# simple_thermostat_2.net
KiCad netlist of a schematic drawn in EAGLE
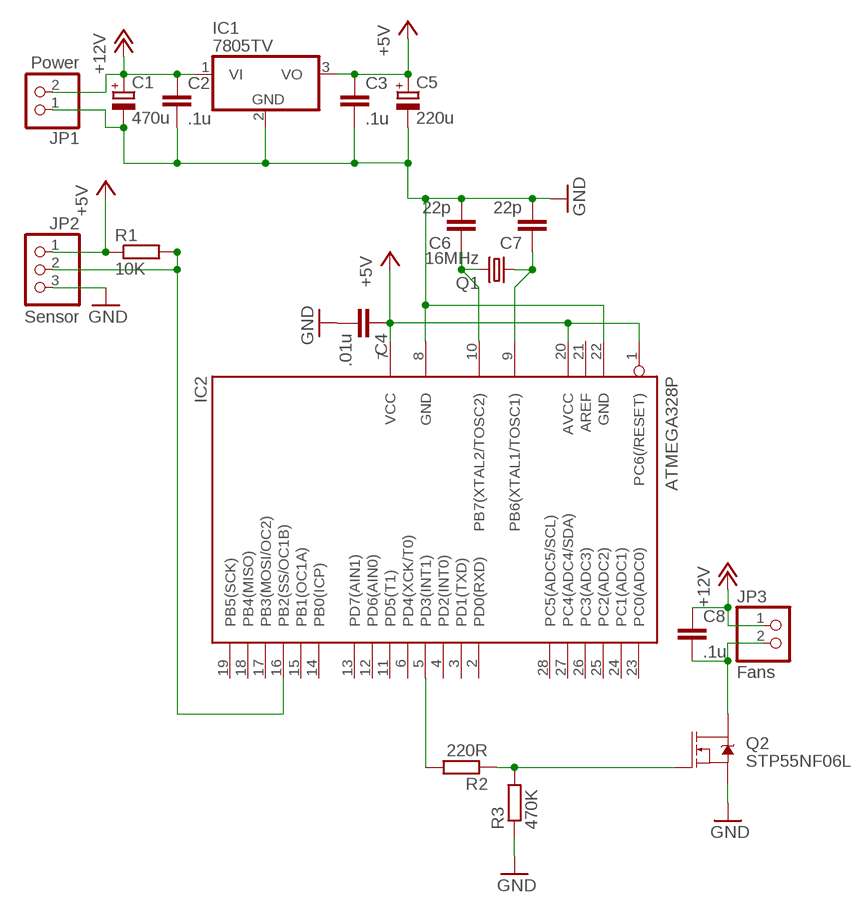
[diagram p0: schematic, sheet 1]

(export (version "E")
  (design (tool "Eeschema 10.0.6"))
  (components
    (comp (ref "C1")
      (value "470u")
      (footprint "eagle-import:E3,5-10")
      (libsource (lib "eagle-import") (part "CPOL-EUE3.5-10"))
    )
    (comp (ref "C2")
      (value ".1u")
      (footprint "eagle-import:C025-024X044")
      (libsource (lib "eagle-import") (part "C-EU025-024X044"))
    )
    (comp (ref "C3")
      (value ".1u")
      (footprint "eagle-import:C025-024X044")
      (libsource (lib "eagle-import") (part "C-EU025-024X044"))
    )
    (comp (ref "C4")
      (value ".01u")
      (footprint "eagle-import:C025-024X044")
      (libsource (lib "eagle-import") (part "C-EU025-024X044"))
    )
    (comp (ref "C5")
      (value "220u")
      (footprint "eagle-import:E2,5-7")
      (libsource (lib "eagle-import") (part "CPOL-EUE2.5-7"))
    )
    (comp (ref "C6")
      (value "22p")
      (footprint "eagle-import:C025-024X044")
      (libsource (lib "eagle-import") (part "C-EU025-024X044"))
    )
    (comp (ref "C7")
      (value "22p")
      (footprint "eagle-import:C025-024X044")
      (libsource (lib "eagle-import") (part "C-EU025-024X044"))
    )
    (comp (ref "C8")
      (value ".1u")
      (footprint "eagle-import:C025-024X044")
      (libsource (lib "eagle-import") (part "C-EU025-024X044"))
    )
    (comp (ref "IC1")
      (value "7805TV")
      (footprint "eagle-import:TO220V")
      (libsource (lib "eagle-import") (part "78TV05"))
    )
    (comp (ref "IC2")
      (value "ATMEGA328P")
      (footprint "eagle-import:DIL28-3")
      (libsource (lib "eagle-import") (part "MEGA8-P"))
    )
    (comp (ref "JP1")
      (value "Power")
      (footprint "eagle-import:1X02")
      (libsource (lib "eagle-import") (part "PINHD-1X2"))
    )
    (comp (ref "JP2")
      (value "Sensor")
      (footprint "eagle-import:1X03")
      (libsource (lib "eagle-import") (part "PINHD-1X3"))
    )
    (comp (ref "JP3")
      (value "Fans")
      (footprint "eagle-import:1X02")
      (libsource (lib "eagle-import") (part "PINHD-1X2"))
    )
    (comp (ref "Q1")
      (value "16MHz")
      (footprint "eagle-import:HC18U-V")
      (libsource (lib "eagle-import") (part "CRYSTALHC18U-V"))
    )
    (comp (ref "Q2")
      (value "STP55NF06L")
      (footprint "eagle-import:TO220V")
      (libsource (lib "eagle-import") (part "MOSFET-NCH-FQP30N06L"))
    )
    (comp (ref "R1")
      (value "10K")
      (footprint "eagle-import:0207_7")
      (libsource (lib "eagle-import") (part "R-EU_0207/7"))
    )
    (comp (ref "R2")
      (value "220R")
      (footprint "eagle-import:0207_7")
      (libsource (lib "eagle-import") (part "R-EU_0207/7"))
    )
    (comp (ref "R3")
      (value "470K")
      (footprint "eagle-import:0207_7")
      (libsource (lib "eagle-import") (part "R-EU_0207/7"))
    )
  )
  (nets
    (net (code "1") (name "+5V") (class "Default")
      (node (ref "C3") (pin "1") (pinfunction "1_1") (pintype "passive"))
      (node (ref "C4") (pin "1") (pinfunction "1_1") (pintype "passive"))
      (node (ref "C5") (pin "+") (pinfunction "+_+") (pintype "passive"))
      (node (ref "IC1") (pin "3") (pinfunction "VO_3") (pintype "passive"))
      (node (ref "IC2") (pin "1") (pinfunction "PC6(/RESET)_1") (pintype "bidirectional"))
      (node (ref "IC2") (pin "20") (pinfunction "AVCC_20") (pintype "power_in"))
      (node (ref "IC2") (pin "7") (pinfunction "VCC_7") (pintype "power_in"))
      (node (ref "JP2") (pin "1") (pinfunction "1_1") (pintype "passive"))
      (node (ref "R1") (pin "1") (pinfunction "1_1") (pintype "passive"))
    )
    (net (code "2") (name "+12V") (class "Default")
      (node (ref "C1") (pin "+") (pinfunction "+_+") (pintype "passive"))
      (node (ref "C2") (pin "1") (pinfunction "1_1") (pintype "passive"))
      (node (ref "C8") (pin "1") (pinfunction "1_1") (pintype "passive"))
      (node (ref "IC1") (pin "1") (pinfunction "VI_1") (pintype "input"))
      (node (ref "JP1") (pin "2") (pinfunction "2_2") (pintype "passive"))
      (node (ref "JP3") (pin "1") (pinfunction "1_1") (pintype "passive"))
    )
    (net (code "3") (name "GND") (class "Default")
      (node (ref "C1") (pin "-") (pinfunction "-_-") (pintype "passive"))
      (node (ref "C2") (pin "2") (pinfunction "2_2") (pintype "passive"))
      (node (ref "C3") (pin "2") (pinfunction "2_2") (pintype "passive"))
      (node (ref "C4") (pin "2") (pinfunction "2_2") (pintype "passive"))
      (node (ref "C5") (pin "-") (pinfunction "-_-") (pintype "passive"))
      (node (ref "C6") (pin "2") (pinfunction "2_2") (pintype "passive"))
      (node (ref "C7") (pin "2") (pinfunction "2_2") (pintype "passive"))
      (node (ref "IC1") (pin "2") (pinfunction "GND_2") (pintype "passive"))
      (node (ref "IC2") (pin "22") (pinfunction "GND_22") (pintype "power_in"))
      (node (ref "IC2") (pin "8") (pinfunction "GND_8") (pintype "power_in"))
      (node (ref "JP1") (pin "1") (pinfunction "1_1") (pintype "passive"))
      (node (ref "JP2") (pin "3") (pinfunction "3_3") (pintype "passive"))
      (node (ref "Q2") (pin "3") (pinfunction "S_3") (pintype "bidirectional"))
      (node (ref "R3") (pin "1") (pinfunction "1_1") (pintype "passive"))
    )
    (net (code "4") (name "Net-(IC2-PB2(SS{slash}OC1B))") (class "Default")
      (node (ref "IC2") (pin "16") (pinfunction "PB2(SS/OC1B)_16") (pintype "bidirectional"))
      (node (ref "JP2") (pin "2") (pinfunction "2_2") (pintype "passive"))
      (node (ref "R1") (pin "2") (pinfunction "2_2") (pintype "passive"))
    )
    (net (code "5") (name "Net-(IC2-PB6(XTAL1{slash}TOSC1))") (class "Default")
      (node (ref "C7") (pin "1") (pinfunction "1_1") (pintype "passive"))
      (node (ref "IC2") (pin "9") (pinfunction "PB6(XTAL1/TOSC1)_9") (pintype "bidirectional"))
      (node (ref "Q1") (pin "1") (pinfunction "1_1") (pintype "passive"))
    )
    (net (code "6") (name "Net-(IC2-PB7(XTAL2{slash}TOSC2))") (class "Default")
      (node (ref "C6") (pin "1") (pinfunction "1_1") (pintype "passive"))
      (node (ref "IC2") (pin "10") (pinfunction "PB7(XTAL2/TOSC2)_10") (pintype "bidirectional"))
      (node (ref "Q1") (pin "2") (pinfunction "2_2") (pintype "passive"))
    )
    (net (code "7") (name "Net-(IC2-PD3(INT1))") (class "Default")
      (node (ref "IC2") (pin "5") (pinfunction "PD3(INT1)_5") (pintype "bidirectional"))
      (node (ref "R2") (pin "2") (pinfunction "2_2") (pintype "passive"))
    )
    (net (code "8") (name "Net-(Q2-D)") (class "Default")
      (node (ref "C8") (pin "2") (pinfunction "2_2") (pintype "passive"))
      (node (ref "JP3") (pin "2") (pinfunction "2_2") (pintype "passive"))
      (node (ref "Q2") (pin "2") (pinfunction "D_2") (pintype "bidirectional"))
    )
    (net (code "9") (name "Net-(Q2-G)") (class "Default")
      (node (ref "Q2") (pin "1") (pinfunction "G_1") (pintype "bidirectional"))
      (node (ref "R2") (pin "1") (pinfunction "1_1") (pintype "passive"))
      (node (ref "R3") (pin "2") (pinfunction "2_2") (pintype "passive"))
    )
    (net (code "10") (name "unconnected-(IC2-AREF-Pad21)") (class "Default")
      (node (ref "IC2") (pin "21") (pinfunction "AREF_21") (pintype "passive"))
    )
    (net (code "11") (name "unconnected-(IC2-PB0(ICP)-Pad14)") (class "Default")
      (node (ref "IC2") (pin "14") (pinfunction "PB0(ICP)_14") (pintype "bidirectional"))
    )
    (net (code "12") (name "unconnected-(IC2-PB1(OC1A)-Pad15)") (class "Default")
      (node (ref "IC2") (pin "15") (pinfunction "PB1(OC1A)_15") (pintype "bidirectional"))
    )
    (net (code "13") (name "unconnected-(IC2-PB3(MOSI{slash}OC2)-Pad17)") (class "Default")
      (node (ref "IC2") (pin "17") (pinfunction "PB3(MOSI/OC2)_17") (pintype "bidirectional"))
    )
    (net (code "14") (name "unconnected-(IC2-PB4(MISO)-Pad18)") (class "Default")
      (node (ref "IC2") (pin "18") (pinfunction "PB4(MISO)_18") (pintype "bidirectional"))
    )
    (net (code "15") (name "unconnected-(IC2-PB5(SCK)-Pad19)") (class "Default")
      (node (ref "IC2") (pin "19") (pinfunction "PB5(SCK)_19") (pintype "bidirectional"))
    )
    (net (code "16") (name "unconnected-(IC2-PC0(ADC0)-Pad23)") (class "Default")
      (node (ref "IC2") (pin "23") (pinfunction "PC0(ADC0)_23") (pintype "bidirectional"))
    )
    (net (code "17") (name "unconnected-(IC2-PC1(ADC1)-Pad24)") (class "Default")
      (node (ref "IC2") (pin "24") (pinfunction "PC1(ADC1)_24") (pintype "bidirectional"))
    )
    (net (code "18") (name "unconnected-(IC2-PC2(ADC2)-Pad25)") (class "Default")
      (node (ref "IC2") (pin "25") (pinfunction "PC2(ADC2)_25") (pintype "bidirectional"))
    )
    (net (code "19") (name "unconnected-(IC2-PC3(ADC3)-Pad26)") (class "Default")
      (node (ref "IC2") (pin "26") (pinfunction "PC3(ADC3)_26") (pintype "bidirectional"))
    )
    (net (code "20") (name "unconnected-(IC2-PC4(ADC4{slash}SDA)-Pad27)") (class "Default")
      (node (ref "IC2") (pin "27") (pinfunction "PC4(ADC4/SDA)_27") (pintype "bidirectional"))
    )
    (net (code "21") (name "unconnected-(IC2-PC5(ADC5{slash}SCL)-Pad28)") (class "Default")
      (node (ref "IC2") (pin "28") (pinfunction "PC5(ADC5/SCL)_28") (pintype "bidirectional"))
    )
    (net (code "22") (name "unconnected-(IC2-PD0(RXD)-Pad2)") (class "Default")
      (node (ref "IC2") (pin "2") (pinfunction "PD0(RXD)_2") (pintype "bidirectional"))
    )
    (net (code "23") (name "unconnected-(IC2-PD1(TXD)-Pad3)") (class "Default")
      (node (ref "IC2") (pin "3") (pinfunction "PD1(TXD)_3") (pintype "bidirectional"))
    )
    (net (code "24") (name "unconnected-(IC2-PD2(INT0)-Pad4)") (class "Default")
      (node (ref "IC2") (pin "4") (pinfunction "PD2(INT0)_4") (pintype "bidirectional"))
    )
    (net (code "25") (name "unconnected-(IC2-PD4(XCK{slash}T0)-Pad6)") (class "Default")
      (node (ref "IC2") (pin "6") (pinfunction "PD4(XCK/T0)_6") (pintype "bidirectional"))
    )
    (net (code "26") (name "unconnected-(IC2-PD5(T1)-Pad11)") (class "Default")
      (node (ref "IC2") (pin "11") (pinfunction "PD5(T1)_11") (pintype "bidirectional"))
    )
    (net (code "27") (name "unconnected-(IC2-PD6(AIN0)-Pad12)") (class "Default")
      (node (ref "IC2") (pin "12") (pinfunction "PD6(AIN0)_12") (pintype "bidirectional"))
    )
    (net (code "28") (name "unconnected-(IC2-PD7(AIN1)-Pad13)") (class "Default")
      (node (ref "IC2") (pin "13") (pinfunction "PD7(AIN1)_13") (pintype "bidirectional"))
    )
  )
)
